# Encoder.net
KiCad netlist of a schematic drawn in Altium Designer
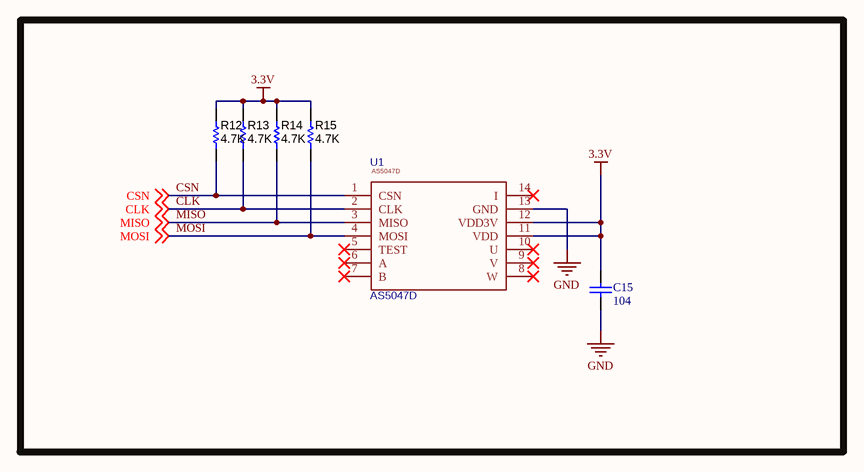
[diagram p0: Encoder.SchDoc]

(export (version "E")
  (design (tool "Eeschema 10.0.6"))
  (components
    (comp (ref "C15")
      (value "104")
      (footprint "TU_SMD_0805")
      (libsource (lib "MH_DA_THU_VIEN_16122016") (part "TU_SMD_0805_MH"))
    )
    (comp (ref "R12")
      (value "4.7K")
      (footprint "0805_HV")
      (description "RES, 100, 1%, 0.1 W, 0402")
      (fields
        (field (name "PARTNUMBER") "ERJ-2RKF1000X")
        (field (name "MANUFACTURER") "Panasonic")
        (field (name "PUBLISHER") "Texas Instruments")
      )
      (libsource (lib "mySch") (part "R nho"))
    )
    (comp (ref "R13")
      (value "4.7K")
      (footprint "0805_HV")
      (description "RES, 100, 1%, 0.1 W, 0402")
      (fields
        (field (name "PARTNUMBER") "ERJ-2RKF1000X")
        (field (name "MANUFACTURER") "Panasonic")
        (field (name "PUBLISHER") "Texas Instruments")
      )
      (libsource (lib "mySch") (part "R nho"))
    )
    (comp (ref "R14")
      (value "4.7K")
      (footprint "0805_HV")
      (description "RES, 100, 1%, 0.1 W, 0402")
      (fields
        (field (name "PARTNUMBER") "ERJ-2RKF1000X")
        (field (name "MANUFACTURER") "Panasonic")
        (field (name "PUBLISHER") "Texas Instruments")
      )
      (libsource (lib "mySch") (part "R nho"))
    )
    (comp (ref "R15")
      (value "4.7K")
      (footprint "0805_HV")
      (description "RES, 100, 1%, 0.1 W, 0402")
      (fields
        (field (name "PARTNUMBER") "ERJ-2RKF1000X")
        (field (name "MANUFACTURER") "Panasonic")
        (field (name "PUBLISHER") "Texas Instruments")
      )
      (libsource (lib "mySch") (part "R nho"))
    )
    (comp (ref "U1")
      (value "AS5047D")
      (footprint "TSSOP14")
      (fields (field (name "BOM_MANUFACTURER PART") "?"))
      (libsource (lib "mySch") (part "AS5047D"))
    )
  )
  (nets
    (net (code "1") (name "3.3V") (class "Default")
      (node (ref "C15") (pin "2") (pinfunction "2_2") (pintype "passive"))
      (node (ref "R12") (pin "2") (pinfunction "2_2") (pintype "passive"))
      (node (ref "R13") (pin "2") (pinfunction "2_2") (pintype "passive"))
      (node (ref "R14") (pin "2") (pinfunction "2_2") (pintype "passive"))
      (node (ref "R15") (pin "2") (pinfunction "2_2") (pintype "passive"))
      (node (ref "U1") (pin "11") (pinfunction "VDD_11") (pintype "passive"))
      (node (ref "U1") (pin "12") (pinfunction "VDD3V_12") (pintype "passive"))
    )
    (net (code "2") (name "CLK") (class "Default")
      (node (ref "R13") (pin "1") (pinfunction "1_1") (pintype "passive"))
      (node (ref "U1") (pin "2") (pinfunction "CLK_2") (pintype "passive"))
    )
    (net (code "3") (name "CSN") (class "Default")
      (node (ref "R12") (pin "1") (pinfunction "1_1") (pintype "passive"))
      (node (ref "U1") (pin "1") (pinfunction "CSN_1") (pintype "passive"))
    )
    (net (code "4") (name "GND") (class "Default")
      (node (ref "C15") (pin "1") (pinfunction "1_1") (pintype "passive"))
      (node (ref "U1") (pin "13") (pinfunction "GND_13") (pintype "passive"))
    )
    (net (code "5") (name "MISO") (class "Default")
      (node (ref "R14") (pin "1") (pinfunction "1_1") (pintype "passive"))
      (node (ref "U1") (pin "3") (pinfunction "MISO_3") (pintype "passive"))
    )
    (net (code "6") (name "MOSI") (class "Default")
      (node (ref "R15") (pin "1") (pinfunction "1_1") (pintype "passive"))
      (node (ref "U1") (pin "4") (pinfunction "MOSI_4") (pintype "passive"))
    )
    (net (code "7") (name "unconnected-(U1-A-Pad6)") (class "Default")
      (node (ref "U1") (pin "6") (pinfunction "A_6") (pintype "passive+no_connect"))
    )
    (net (code "8") (name "unconnected-(U1-B-Pad7)") (class "Default")
      (node (ref "U1") (pin "7") (pinfunction "B_7") (pintype "passive+no_connect"))
    )
    (net (code "9") (name "unconnected-(U1-I-Pad14)") (class "Default")
      (node (ref "U1") (pin "14") (pinfunction "I_14") (pintype "passive+no_connect"))
    )
    (net (code "10") (name "unconnected-(U1-TEST-Pad5)") (class "Default")
      (node (ref "U1") (pin "5") (pinfunction "TEST_5") (pintype "passive+no_connect"))
    )
    (net (code "11") (name "unconnected-(U1-U-Pad10)") (class "Default")
      (node (ref "U1") (pin "10") (pinfunction "U_10") (pintype "passive+no_connect"))
    )
    (net (code "12") (name "unconnected-(U1-V-Pad9)") (class "Default")
      (node (ref "U1") (pin "9") (pinfunction "V_9") (pintype "passive+no_connect"))
    )
    (net (code "13") (name "unconnected-(U1-W-Pad8)") (class "Default")
      (node (ref "U1") (pin "8") (pinfunction "W_8") (pintype "passive+no_connect"))
    )
  )
)
